# SCH_usb_board.net
KiCad netlist of a schematic drawn in EasyEDA
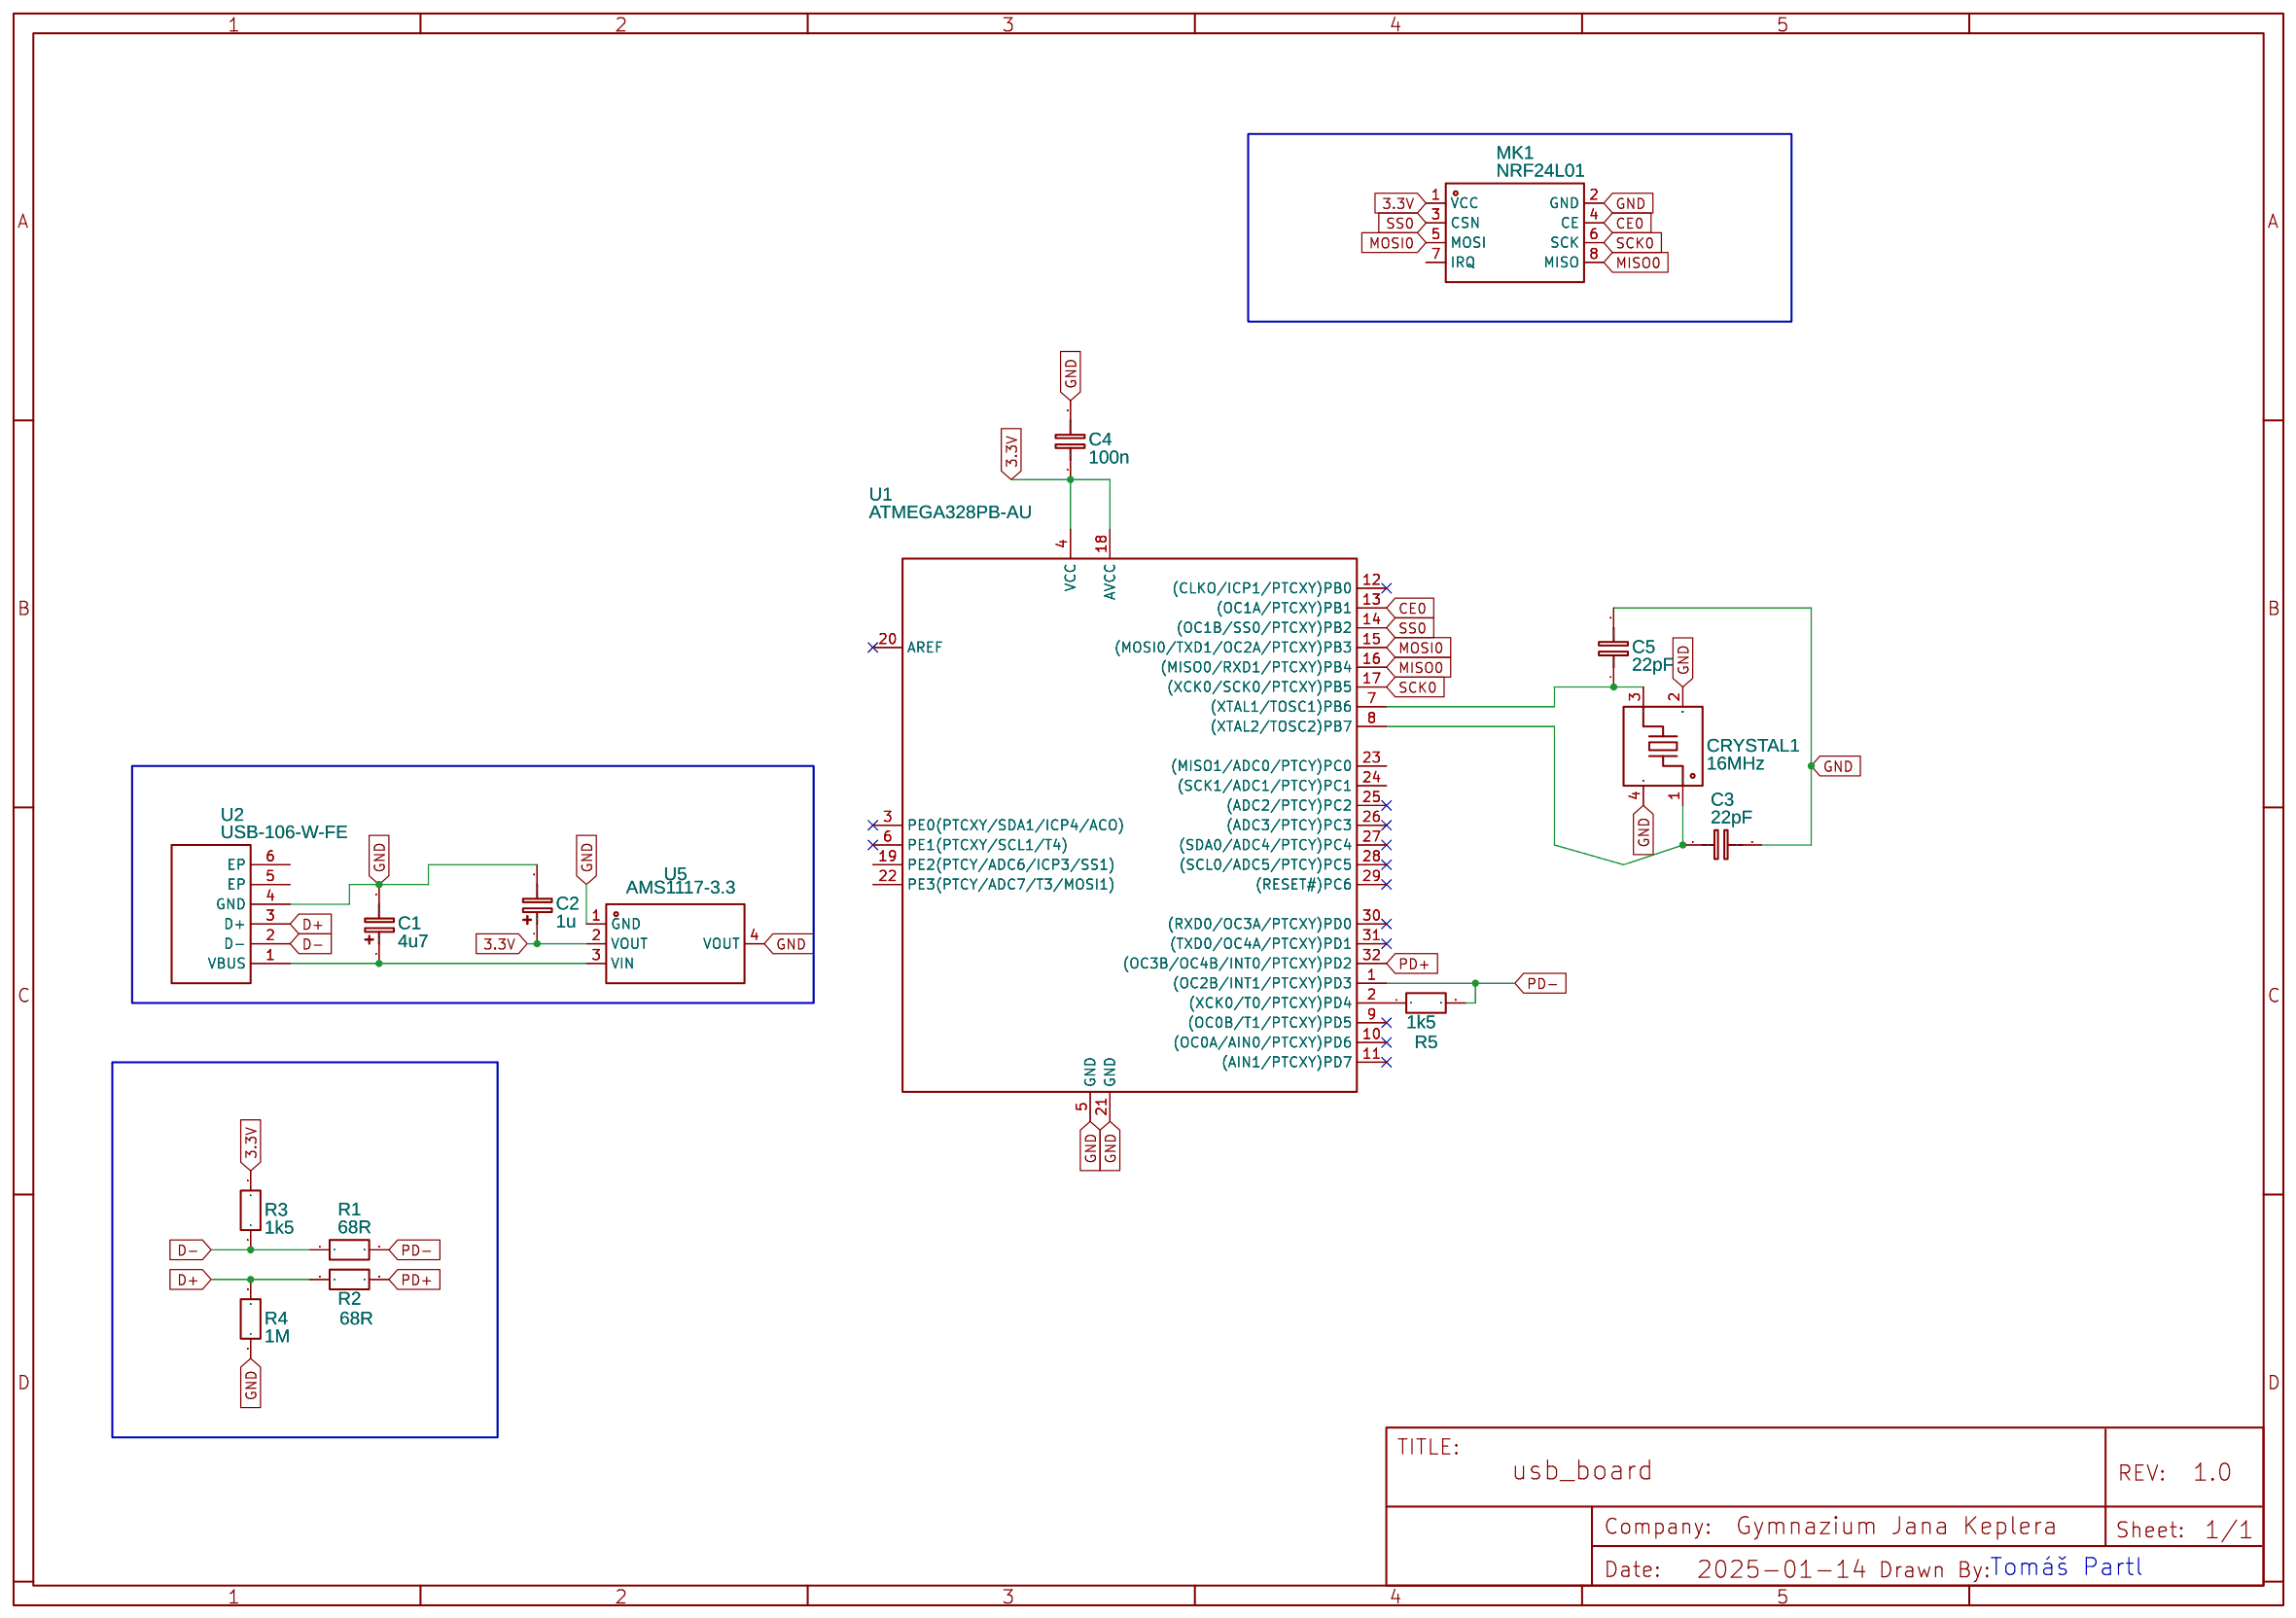
[diagram p0: schematic sheet]

(export (version "E")
  (design (tool "Eeschema 10.0.6"))
  (components
    (comp (ref "C1") (value "4u7") (libsource (lib "") (part "C_Tan_SMD_A_EU")))
    (comp (ref "C2") (value "1u") (libsource (lib "") (part "C_Tan_SMD_A_EU_1")))
    (comp (ref "C3") (value "22pF") (libsource (lib "") (part "C_0603_EU_2")))
    (comp (ref "C4") (value "100n") (libsource (lib "") (part "C_0603_EU")))
    (comp (ref "C5") (value "22pF") (libsource (lib "") (part "C_0603_EU_1")))
    (comp (ref "CRYSTAL1")
      (value "16MHz")
      (fields (field (name "Manufacturer Part") "CM4016M00010001") (field (name "Manufacturer") "HUAXIN(华昕)"))
      (libsource (lib "") (part "CM4016M00010001"))
    )
    (comp (ref "MK1")
      (value "NRF24L01")
      (fields (field (name "Manufacturer Part") "NF-04") (field (name "Manufacturer") "Ai-Thinker(安信可)"))
      (libsource (lib "") (part "NRF24L01"))
    )
    (comp (ref "R1") (value "68R") (libsource (lib "") (part "R_0603_EU_1")))
    (comp (ref "R2") (value "68R") (libsource (lib "") (part "R_0603_EU_1")))
    (comp (ref "R3") (value "1k5") (libsource (lib "") (part "R_0603_EU")))
    (comp (ref "R4") (value "1M") (libsource (lib "") (part "R_0603_EU")))
    (comp (ref "R5") (value "1k5") (libsource (lib "") (part "R_0603_EU_1")))
    (comp (ref "U1")
      (value "ATMEGA328PB-AU")
      (fields (field (name "Manufacturer") "MICROCHIP(美国微芯)"))
      (libsource (lib "") (part "ATMEGA328PB-AU"))
    )
    (comp (ref "U2")
      (value "USB-106-W-FE")
      (fields (field (name "Manufacturer") "HOOYA(皓宇电子)"))
      (libsource (lib "") (part "USB-106-W-FE"))
    )
    (comp (ref "U5")
      (value "AMS1117-3.3")
      (fields (field (name "Manufacturer") "AMS"))
      (libsource (lib "") (part "AMS1117-3.3"))
    )
  )
  (nets
    (net (code "1") (name "3.3V") (class "Default")
      (node (ref "C2") (pin "1") (pinfunction "1_1") (pintype "unspecified"))
      (node (ref "C4") (pin "1") (pinfunction "1_1") (pintype "unspecified"))
      (node (ref "MK1") (pin "1") (pinfunction "VCC_1") (pintype "unspecified"))
      (node (ref "R3") (pin "2") (pinfunction "2_2") (pintype "unspecified"))
      (node (ref "U1") (pin "18") (pinfunction "AVCC_18") (pintype "bidirectional"))
      (node (ref "U1") (pin "4") (pinfunction "VCC_4") (pintype "bidirectional"))
      (node (ref "U5") (pin "2") (pinfunction "VOUT_2") (pintype "unspecified"))
    )
    (net (code "2") (name "CE0") (class "Default")
      (node (ref "MK1") (pin "4") (pinfunction "CE_4") (pintype "unspecified"))
      (node (ref "U1") (pin "13") (pinfunction "(OC1A/PTCXY)PB1_13") (pintype "bidirectional"))
    )
    (net (code "3") (name "D+") (class "Default")
      (node (ref "R2") (pin "1") (pinfunction "1_1") (pintype "unspecified"))
      (node (ref "R4") (pin "2") (pinfunction "2_2") (pintype "unspecified"))
      (node (ref "U2") (pin "3") (pinfunction "D+_3") (pintype "unspecified"))
    )
    (net (code "4") (name "D-") (class "Default")
      (node (ref "R1") (pin "1") (pinfunction "1_1") (pintype "unspecified"))
      (node (ref "R3") (pin "1") (pinfunction "1_1") (pintype "unspecified"))
      (node (ref "U2") (pin "2") (pinfunction "D-_2") (pintype "unspecified"))
    )
    (net (code "5") (name "GND") (class "Default")
      (node (ref "C1") (pin "2") (pinfunction "2_2") (pintype "unspecified"))
      (node (ref "C2") (pin "2") (pinfunction "2_2") (pintype "unspecified"))
      (node (ref "C3") (pin "2") (pinfunction "2_2") (pintype "unspecified"))
      (node (ref "C4") (pin "2") (pinfunction "2_2") (pintype "unspecified"))
      (node (ref "C5") (pin "2") (pinfunction "2_2") (pintype "unspecified"))
      (node (ref "CRYSTAL1") (pin "2") (pinfunction "GND_2") (pintype "input"))
      (node (ref "CRYSTAL1") (pin "4") (pinfunction "GND_4") (pintype "input"))
      (node (ref "MK1") (pin "2") (pinfunction "GND_2") (pintype "unspecified"))
      (node (ref "R4") (pin "1") (pinfunction "1_1") (pintype "unspecified"))
      (node (ref "U1") (pin "21") (pinfunction "GND_21") (pintype "bidirectional"))
      (node (ref "U1") (pin "5") (pinfunction "GND_5") (pintype "bidirectional"))
      (node (ref "U2") (pin "4") (pinfunction "GND_4") (pintype "unspecified"))
      (node (ref "U5") (pin "1") (pinfunction "GND_1") (pintype "unspecified"))
      (node (ref "U5") (pin "4") (pinfunction "VOUT_4") (pintype "unspecified"))
    )
    (net (code "6") (name "MISO0") (class "Default")
      (node (ref "MK1") (pin "8") (pinfunction "MISO_8") (pintype "unspecified"))
      (node (ref "U1") (pin "16") (pinfunction "(MISO0/RXD1/PTCXY)PB4_16") (pintype "bidirectional"))
    )
    (net (code "7") (name "MOSI0") (class "Default")
      (node (ref "MK1") (pin "5") (pinfunction "MOSI_5") (pintype "unspecified"))
      (node (ref "U1") (pin "15") (pinfunction "(MOSI0/TXD1/OC2A/PTCXY)PB3_15") (pintype "bidirectional"))
    )
    (net (code "8") (name "Net-(U1-(XCK0{slash}T0{slash}PTCXY)PD4)") (class "Default")
      (node (ref "R5") (pin "1") (pinfunction "1_1") (pintype "unspecified"))
      (node (ref "U1") (pin "2") (pinfunction "(XCK0/T0/PTCXY)PD4_2") (pintype "bidirectional"))
    )
    (net (code "9") (name "Net-(U1-(XTAL1{slash}TOSC1)PB6)") (class "Default")
      (node (ref "C5") (pin "1") (pinfunction "1_1") (pintype "unspecified"))
      (node (ref "CRYSTAL1") (pin "3") (pinfunction "3_3") (pintype "input"))
      (node (ref "U1") (pin "7") (pinfunction "(XTAL1/TOSC1)PB6_7") (pintype "bidirectional"))
    )
    (net (code "10") (name "Net-(U1-(XTAL2{slash}TOSC2)PB7)") (class "Default")
      (node (ref "C3") (pin "1") (pinfunction "1_1") (pintype "unspecified"))
      (node (ref "CRYSTAL1") (pin "1") (pinfunction "1_1") (pintype "input"))
      (node (ref "U1") (pin "8") (pinfunction "(XTAL2/TOSC2)PB7_8") (pintype "bidirectional"))
    )
    (net (code "11") (name "Net-(U2-VBUS)") (class "Default")
      (node (ref "C1") (pin "1") (pinfunction "1_1") (pintype "unspecified"))
      (node (ref "U2") (pin "1") (pinfunction "VBUS_1") (pintype "unspecified"))
      (node (ref "U5") (pin "3") (pinfunction "VIN_3") (pintype "unspecified"))
    )
    (net (code "12") (name "PD+") (class "Default")
      (node (ref "R2") (pin "2") (pinfunction "2_2") (pintype "unspecified"))
      (node (ref "U1") (pin "32") (pinfunction "(OC3B/OC4B/INT0/PTCXY)PD2_32") (pintype "bidirectional"))
    )
    (net (code "13") (name "PD-") (class "Default")
      (node (ref "R1") (pin "2") (pinfunction "2_2") (pintype "unspecified"))
      (node (ref "R5") (pin "2") (pinfunction "2_2") (pintype "unspecified"))
      (node (ref "U1") (pin "1") (pinfunction "(OC2B/INT1/PTCXY)PD3_1") (pintype "bidirectional"))
    )
    (net (code "14") (name "SCK0") (class "Default")
      (node (ref "MK1") (pin "6") (pinfunction "SCK_6") (pintype "unspecified"))
      (node (ref "U1") (pin "17") (pinfunction "(XCK0/SCK0/PTCXY)PB5_17") (pintype "bidirectional"))
    )
    (net (code "15") (name "SS0") (class "Default")
      (node (ref "MK1") (pin "3") (pinfunction "CSN_3") (pintype "unspecified"))
      (node (ref "U1") (pin "14") (pinfunction "(OC1B/SS0/PTCXY)PB2_14") (pintype "bidirectional"))
    )
    (net (code "16") (name "unconnected-(MK1-IRQ-Pad7)") (class "Default")
      (node (ref "MK1") (pin "7") (pinfunction "IRQ_7") (pintype "unspecified"))
    )
    (net (code "17") (name "unconnected-(U1-(ADC2{slash}PTCY)PC2-Pad25)") (class "Default")
      (node (ref "U1") (pin "25") (pinfunction "(ADC2/PTCY)PC2_25") (pintype "bidirectional+no_connect"))
    )
    (net (code "18") (name "unconnected-(U1-(ADC3{slash}PTCY)PC3-Pad26)") (class "Default")
      (node (ref "U1") (pin "26") (pinfunction "(ADC3/PTCY)PC3_26") (pintype "bidirectional+no_connect"))
    )
    (net (code "19") (name "unconnected-(U1-(AIN1{slash}PTCXY)PD7-Pad11)") (class "Default")
      (node (ref "U1") (pin "11") (pinfunction "(AIN1/PTCXY)PD7_11") (pintype "bidirectional+no_connect"))
    )
    (net (code "20") (name "unconnected-(U1-(CLKO{slash}ICP1{slash}PTCXY)PB0-Pad12)") (class "Default")
      (node (ref "U1") (pin "12") (pinfunction "(CLKO/ICP1/PTCXY)PB0_12") (pintype "bidirectional+no_connect"))
    )
    (net (code "21") (name "unconnected-(U1-(MISO1{slash}ADC0{slash}PTCY)PC0-Pad23)") (class "Default")
      (node (ref "U1") (pin "23") (pinfunction "(MISO1/ADC0/PTCY)PC0_23") (pintype "bidirectional"))
    )
    (net (code "22") (name "unconnected-(U1-(OC0A{slash}AIN0{slash}PTCXY)PD6-Pad10)") (class "Default")
      (node (ref "U1") (pin "10") (pinfunction "(OC0A/AIN0/PTCXY)PD6_10") (pintype "bidirectional+no_connect"))
    )
    (net (code "23") (name "unconnected-(U1-(OC0B{slash}T1{slash}PTCXY)PD5-Pad9)") (class "Default")
      (node (ref "U1") (pin "9") (pinfunction "(OC0B/T1/PTCXY)PD5_9") (pintype "bidirectional+no_connect"))
    )
    (net (code "24") (name "unconnected-(U1-(RESET#)PC6-Pad29)") (class "Default")
      (node (ref "U1") (pin "29") (pinfunction "(RESET#)PC6_29") (pintype "bidirectional+no_connect"))
    )
    (net (code "25") (name "unconnected-(U1-(RXD0{slash}OC3A{slash}PTCXY)PD0-Pad30)") (class "Default")
      (node (ref "U1") (pin "30") (pinfunction "(RXD0/OC3A/PTCXY)PD0_30") (pintype "bidirectional+no_connect"))
    )
    (net (code "26") (name "unconnected-(U1-(SCK1{slash}ADC1{slash}PTCY)PC1-Pad24)") (class "Default")
      (node (ref "U1") (pin "24") (pinfunction "(SCK1/ADC1/PTCY)PC1_24") (pintype "bidirectional"))
    )
    (net (code "27") (name "unconnected-(U1-(SCL0{slash}ADC5{slash}PTCY)PC5-Pad28)") (class "Default")
      (node (ref "U1") (pin "28") (pinfunction "(SCL0/ADC5/PTCY)PC5_28") (pintype "bidirectional+no_connect"))
    )
    (net (code "28") (name "unconnected-(U1-(SDA0{slash}ADC4{slash}PTCY)PC4-Pad27)") (class "Default")
      (node (ref "U1") (pin "27") (pinfunction "(SDA0/ADC4/PTCY)PC4_27") (pintype "bidirectional+no_connect"))
    )
    (net (code "29") (name "unconnected-(U1-(TXD0{slash}OC4A{slash}PTCXY)PD1-Pad31)") (class "Default")
      (node (ref "U1") (pin "31") (pinfunction "(TXD0/OC4A/PTCXY)PD1_31") (pintype "bidirectional+no_connect"))
    )
    (net (code "30") (name "unconnected-(U1-AREF-Pad20)") (class "Default")
      (node (ref "U1") (pin "20") (pinfunction "AREF_20") (pintype "bidirectional+no_connect"))
    )
    (net (code "31") (name "unconnected-(U1-PE0(PTCXY{slash}SDA1{slash}ICP4{slash}ACO)-Pad3)") (class "Default")
      (node (ref "U1") (pin "3") (pinfunction "PE0(PTCXY/SDA1/ICP4/ACO)_3") (pintype "bidirectional+no_connect"))
    )
    (net (code "32") (name "unconnected-(U1-PE1(PTCXY{slash}SCL1{slash}T4)-Pad6)") (class "Default")
      (node (ref "U1") (pin "6") (pinfunction "PE1(PTCXY/SCL1/T4)_6") (pintype "bidirectional+no_connect"))
    )
    (net (code "33") (name "unconnected-(U1-PE2(PTCY{slash}ADC6{slash}ICP3{slash}SS1)-Pad19)") (class "Default")
      (node (ref "U1") (pin "19") (pinfunction "PE2(PTCY/ADC6/ICP3/SS1)_19") (pintype "bidirectional"))
    )
    (net (code "34") (name "unconnected-(U1-PE3(PTCY{slash}ADC7{slash}T3{slash}MOSI1)-Pad22)") (class "Default")
      (node (ref "U1") (pin "22") (pinfunction "PE3(PTCY/ADC7/T3/MOSI1)_22") (pintype "bidirectional"))
    )
    (net (code "35") (name "unconnected-(U2-EP-Pad5)") (class "Default")
      (node (ref "U2") (pin "5") (pinfunction "EP_5") (pintype "unspecified"))
    )
    (net (code "36") (name "unconnected-(U2-EP-Pad6)") (class "Default")
      (node (ref "U2") (pin "6") (pinfunction "EP_6") (pintype "unspecified"))
    )
  )
)
